# adapter_v1_2.net
KiCad netlist of a schematic drawn in EAGLE
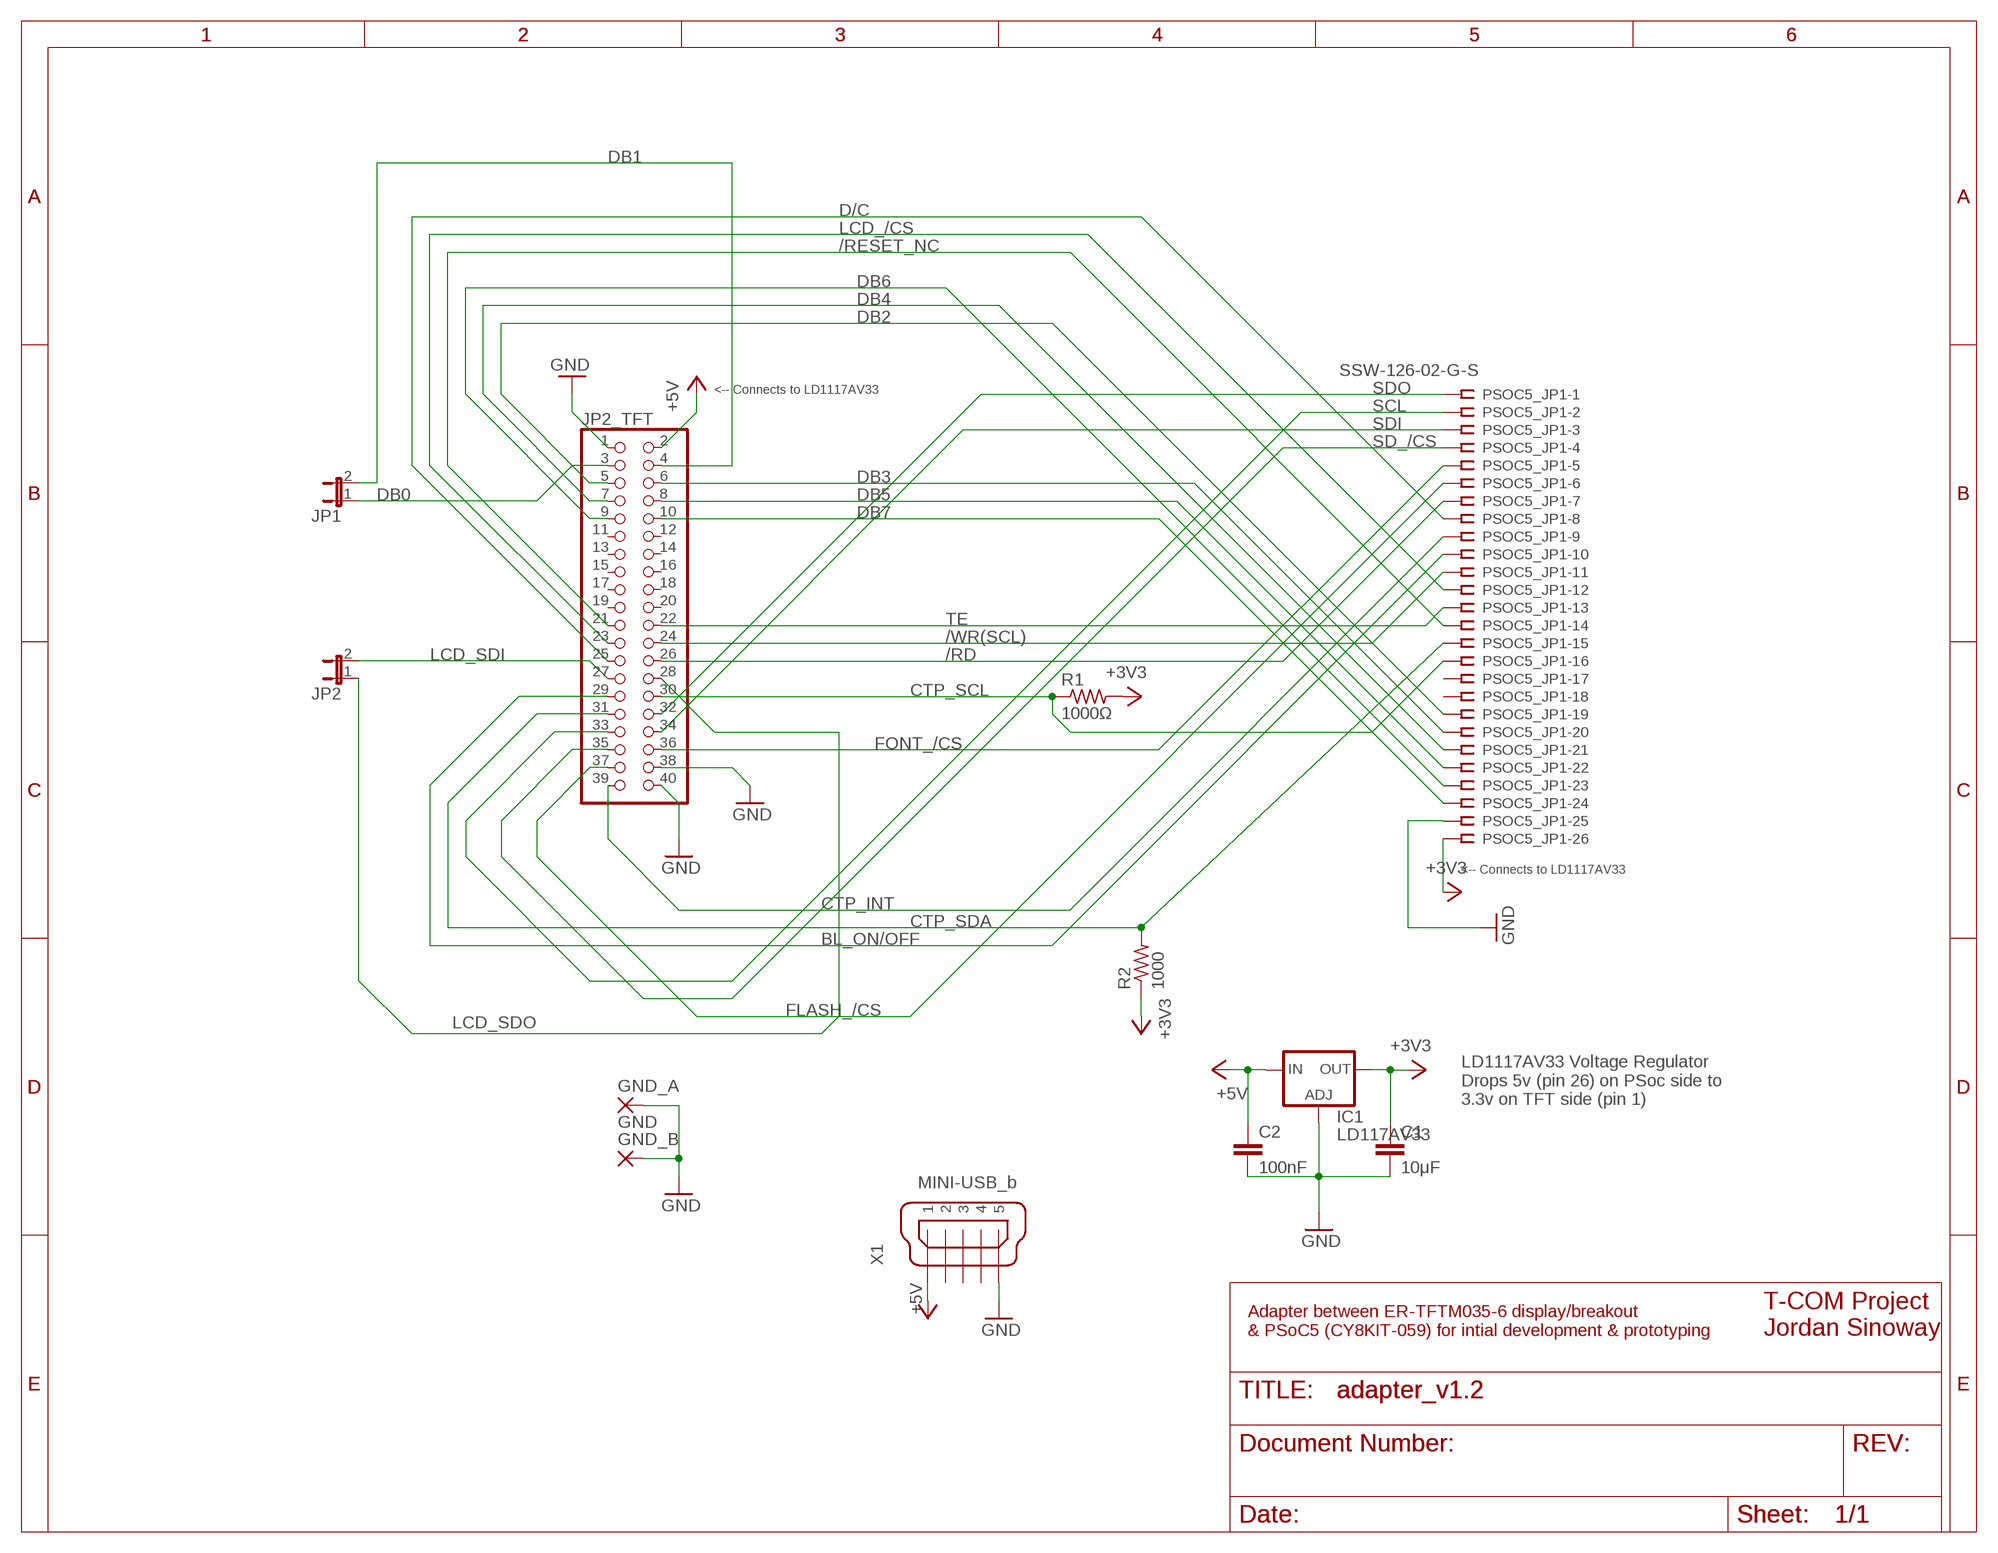
[diagram p0: schematic, sheet 1]

(export (version "E")
  (design (tool "Eeschema 10.0.6"))
  (components
    (comp (ref "C1")
      (value "10μF")
      (footprint "eagle-import:C2.5-2")
      (libsource (lib "eagle-import") (part "C2.5/2"))
    )
    (comp (ref "C2")
      (value "100nF")
      (footprint "eagle-import:C2.5-2")
      (libsource (lib "eagle-import") (part "C2.5/2"))
    )
    (comp (ref "GND_A")
      (value "GND")
      (footprint "eagle-import:SMD2,54-5,08")
      (libsource (lib "eagle-import") (part "SMD5"))
    )
    (comp (ref "GND_B")
      (value "SMD5")
      (footprint "eagle-import:SMD2,54-5,08")
      (libsource (lib "eagle-import") (part "SMD5"))
    )
    (comp (ref "IC1")
      (value "LD117AV33")
      (footprint "eagle-import:TO220L1")
      (libsource (lib "eagle-import") (part "LD117A?V33"))
    )
    (comp (ref "JP1")
      (value "JP1E")
      (footprint "eagle-import:JP1")
      (libsource (lib "eagle-import") (part "JP1E"))
    )
    (comp (ref "JP2")
      (value "JP1E")
      (footprint "eagle-import:JP1")
      (libsource (lib "eagle-import") (part "JP1E"))
    )
    (comp (ref "JP2_TFT")
      (value "PINHD-2X20")
      (footprint "eagle-import:2X20")
      (libsource (lib "eagle-import") (part "PINHD-2X20"))
    )
    (comp (ref "PSOC5_JP1")
      (value "SSW-126-02-G-S")
      (footprint "eagle-import:SSW-126-02-G-S")
      (fields (field (name "MF") "Samtec Inc."))
      (libsource (lib "eagle-import") (part "SSW-126-02-G-S"))
    )
    (comp (ref "R1")
      (value "1000Ω")
      (footprint "eagle-import:0204_7")
      (libsource (lib "eagle-import") (part "R-US_0204/7"))
    )
    (comp (ref "R2")
      (value "1000")
      (footprint "eagle-import:0204_7")
      (libsource (lib "eagle-import") (part "R-US_0204/7"))
    )
    (comp (ref "X1")
      (value "MINI-USB_b")
      (footprint "eagle-import:32005-601")
      (libsource (lib "eagle-import") (part "MINI-USB_SHIELD5P2-32005-601"))
    )
  )
  (nets
    (net (code "1") (name "+3V3") (class "Default")
      (node (ref "C1") (pin "1") (pinfunction "1_1") (pintype "passive"))
      (node (ref "IC1") (pin "2") (pinfunction "OUT_2") (pintype "passive"))
      (node (ref "PSOC5_JP1") (pin "26") (pinfunction "1_26") (pintype "passive"))
      (node (ref "R1") (pin "2") (pinfunction "2_2") (pintype "passive"))
      (node (ref "R2") (pin "1") (pinfunction "1_1") (pintype "passive"))
    )
    (net (code "2") (name "+5V") (class "Default")
      (node (ref "C2") (pin "1") (pinfunction "1_1") (pintype "passive"))
      (node (ref "IC1") (pin "3") (pinfunction "IN_3") (pintype "input"))
      (node (ref "JP2_TFT") (pin "2") (pinfunction "2_2") (pintype "passive"))
      (node (ref "X1") (pin "1") (pinfunction "1_1") (pintype "passive"))
    )
    (net (code "3") (name "/BL_ON{slash}OFF") (class "Default")
      (node (ref "JP2_TFT") (pin "29") (pinfunction "29_29") (pintype "passive"))
      (node (ref "PSOC5_JP1") (pin "10") (pinfunction "1_10") (pintype "passive"))
    )
    (net (code "4") (name "/CTP_INT") (class "Default")
      (node (ref "JP2_TFT") (pin "39") (pinfunction "39_39") (pintype "passive"))
      (node (ref "PSOC5_JP1") (pin "9") (pinfunction "1_9") (pintype "passive"))
    )
    (net (code "5") (name "/CTP_SCL") (class "Default")
      (node (ref "JP2_TFT") (pin "30") (pinfunction "30_30") (pintype "passive"))
      (node (ref "PSOC5_JP1") (pin "16") (pinfunction "1_16") (pintype "passive"))
      (node (ref "R1") (pin "1") (pinfunction "1_1") (pintype "passive"))
    )
    (net (code "6") (name "/CTP_SDA") (class "Default")
      (node (ref "JP2_TFT") (pin "31") (pinfunction "31_31") (pintype "passive"))
      (node (ref "PSOC5_JP1") (pin "15") (pinfunction "1_15") (pintype "passive"))
      (node (ref "R2") (pin "2") (pinfunction "2_2") (pintype "passive"))
    )
    (net (code "7") (name "/DB0") (class "Default")
      (node (ref "JP1") (pin "1") (pinfunction "1_1") (pintype "passive"))
      (node (ref "JP2_TFT") (pin "3") (pinfunction "3_3") (pintype "passive"))
    )
    (net (code "8") (name "/DB1") (class "Default")
      (node (ref "JP1") (pin "2") (pinfunction "2_2") (pintype "passive"))
      (node (ref "JP2_TFT") (pin "4") (pinfunction "4_4") (pintype "passive"))
    )
    (net (code "9") (name "/DB2") (class "Default")
      (node (ref "JP2_TFT") (pin "5") (pinfunction "5_5") (pintype "passive"))
      (node (ref "PSOC5_JP1") (pin "19") (pinfunction "1_19") (pintype "passive"))
    )
    (net (code "10") (name "/DB3") (class "Default")
      (node (ref "JP2_TFT") (pin "6") (pinfunction "6_6") (pintype "passive"))
      (node (ref "PSOC5_JP1") (pin "20") (pinfunction "1_20") (pintype "passive"))
    )
    (net (code "11") (name "/DB4") (class "Default")
      (node (ref "JP2_TFT") (pin "7") (pinfunction "7_7") (pintype "passive"))
      (node (ref "PSOC5_JP1") (pin "21") (pinfunction "1_21") (pintype "passive"))
    )
    (net (code "12") (name "/DB5") (class "Default")
      (node (ref "JP2_TFT") (pin "8") (pinfunction "8_8") (pintype "passive"))
      (node (ref "PSOC5_JP1") (pin "22") (pinfunction "1_22") (pintype "passive"))
    )
    (net (code "13") (name "/DB6") (class "Default")
      (node (ref "JP2_TFT") (pin "9") (pinfunction "9_9") (pintype "passive"))
      (node (ref "PSOC5_JP1") (pin "23") (pinfunction "1_23") (pintype "passive"))
    )
    (net (code "14") (name "/DB7") (class "Default")
      (node (ref "JP2_TFT") (pin "10") (pinfunction "10_10") (pintype "passive"))
      (node (ref "PSOC5_JP1") (pin "24") (pinfunction "1_24") (pintype "passive"))
    )
    (net (code "15") (name "/D{slash}C") (class "Default")
      (node (ref "JP2_TFT") (pin "25") (pinfunction "25_25") (pintype "passive"))
      (node (ref "PSOC5_JP1") (pin "8") (pinfunction "1_8") (pintype "passive"))
    )
    (net (code "16") (name "/FLASH_{slash}CS") (class "Default")
      (node (ref "JP2_TFT") (pin "37") (pinfunction "37_37") (pintype "passive"))
      (node (ref "PSOC5_JP1") (pin "6") (pinfunction "1_6") (pintype "passive"))
    )
    (net (code "17") (name "/FONT_{slash}CS") (class "Default")
      (node (ref "JP2_TFT") (pin "36") (pinfunction "36_36") (pintype "passive"))
      (node (ref "PSOC5_JP1") (pin "5") (pinfunction "1_5") (pintype "passive"))
    )
    (net (code "18") (name "/LCD_SDI") (class "Default")
      (node (ref "JP2") (pin "2") (pinfunction "2_2") (pintype "passive"))
      (node (ref "JP2_TFT") (pin "27") (pinfunction "27_27") (pintype "passive"))
    )
    (net (code "19") (name "/LCD_SDO") (class "Default")
      (node (ref "JP2") (pin "1") (pinfunction "1_1") (pintype "passive"))
      (node (ref "JP2_TFT") (pin "28") (pinfunction "28_28") (pintype "passive"))
    )
    (net (code "20") (name "/LCD_{slash}CS") (class "Default")
      (node (ref "JP2_TFT") (pin "23") (pinfunction "23_23") (pintype "passive"))
      (node (ref "PSOC5_JP1") (pin "12") (pinfunction "1_12") (pintype "passive"))
    )
    (net (code "21") (name "/SCL") (class "Default")
      (node (ref "JP2_TFT") (pin "33") (pinfunction "33_33") (pintype "passive"))
      (node (ref "PSOC5_JP1") (pin "2") (pinfunction "1_2") (pintype "passive"))
    )
    (net (code "22") (name "/SDI") (class "Default")
      (node (ref "JP2_TFT") (pin "34") (pinfunction "34_34") (pintype "passive"))
      (node (ref "PSOC5_JP1") (pin "3") (pinfunction "1_3") (pintype "passive"))
    )
    (net (code "23") (name "/SDO") (class "Default")
      (node (ref "JP2_TFT") (pin "32") (pinfunction "32_32") (pintype "passive"))
      (node (ref "PSOC5_JP1") (pin "1") (pinfunction "1_1") (pintype "passive"))
    )
    (net (code "24") (name "/SD_{slash}CS") (class "Default")
      (node (ref "JP2_TFT") (pin "35") (pinfunction "35_35") (pintype "passive"))
      (node (ref "PSOC5_JP1") (pin "4") (pinfunction "1_4") (pintype "passive"))
    )
    (net (code "25") (name "/TE") (class "Default")
      (node (ref "JP2_TFT") (pin "22") (pinfunction "22_22") (pintype "passive"))
      (node (ref "PSOC5_JP1") (pin "13") (pinfunction "1_13") (pintype "passive"))
    )
    (net (code "26") (name "/{slash}RD") (class "Default")
      (node (ref "JP2_TFT") (pin "26") (pinfunction "26_26") (pintype "passive"))
      (node (ref "PSOC5_JP1") (pin "7") (pinfunction "1_7") (pintype "passive"))
    )
    (net (code "27") (name "/{slash}RESET_NC") (class "Default")
      (node (ref "JP2_TFT") (pin "21") (pinfunction "21_21") (pintype "passive"))
      (node (ref "PSOC5_JP1") (pin "14") (pinfunction "1_14") (pintype "passive"))
    )
    (net (code "28") (name "/{slash}WR(SCL)") (class "Default")
      (node (ref "JP2_TFT") (pin "24") (pinfunction "24_24") (pintype "passive"))
      (node (ref "PSOC5_JP1") (pin "11") (pinfunction "1_11") (pintype "passive"))
    )
    (net (code "29") (name "GND") (class "Default")
      (node (ref "C1") (pin "2") (pinfunction "2_2") (pintype "passive"))
      (node (ref "C2") (pin "2") (pinfunction "2_2") (pintype "passive"))
      (node (ref "GND_A") (pin "1") (pinfunction "P_1") (pintype "passive"))
      (node (ref "GND_B") (pin "1") (pinfunction "P_1") (pintype "passive"))
      (node (ref "IC1") (pin "1") (pinfunction "ADJ_1") (pintype "input"))
      (node (ref "JP2_TFT") (pin "1") (pinfunction "1_1") (pintype "passive"))
      (node (ref "JP2_TFT") (pin "38") (pinfunction "38_38") (pintype "passive"))
      (node (ref "JP2_TFT") (pin "40") (pinfunction "40_40") (pintype "passive"))
      (node (ref "PSOC5_JP1") (pin "25") (pinfunction "1_25") (pintype "passive"))
      (node (ref "X1") (pin "5") (pinfunction "5_5") (pintype "passive"))
    )
    (net (code "30") (name "unconnected-(JP2_TFT-Pad11)") (class "Default")
      (node (ref "JP2_TFT") (pin "11") (pinfunction "11_11") (pintype "passive"))
    )
    (net (code "31") (name "unconnected-(JP2_TFT-Pad12)") (class "Default")
      (node (ref "JP2_TFT") (pin "12") (pinfunction "12_12") (pintype "passive"))
    )
    (net (code "32") (name "unconnected-(JP2_TFT-Pad13)") (class "Default")
      (node (ref "JP2_TFT") (pin "13") (pinfunction "13_13") (pintype "passive"))
    )
    (net (code "33") (name "unconnected-(JP2_TFT-Pad14)") (class "Default")
      (node (ref "JP2_TFT") (pin "14") (pinfunction "14_14") (pintype "passive"))
    )
    (net (code "34") (name "unconnected-(JP2_TFT-Pad15)") (class "Default")
      (node (ref "JP2_TFT") (pin "15") (pinfunction "15_15") (pintype "passive"))
    )
    (net (code "35") (name "unconnected-(JP2_TFT-Pad16)") (class "Default")
      (node (ref "JP2_TFT") (pin "16") (pinfunction "16_16") (pintype "passive"))
    )
    (net (code "36") (name "unconnected-(JP2_TFT-Pad17)") (class "Default")
      (node (ref "JP2_TFT") (pin "17") (pinfunction "17_17") (pintype "passive"))
    )
    (net (code "37") (name "unconnected-(JP2_TFT-Pad18)") (class "Default")
      (node (ref "JP2_TFT") (pin "18") (pinfunction "18_18") (pintype "passive"))
    )
    (net (code "38") (name "unconnected-(JP2_TFT-Pad19)") (class "Default")
      (node (ref "JP2_TFT") (pin "19") (pinfunction "19_19") (pintype "passive"))
    )
    (net (code "39") (name "unconnected-(JP2_TFT-Pad20)") (class "Default")
      (node (ref "JP2_TFT") (pin "20") (pinfunction "20_20") (pintype "passive"))
    )
    (net (code "40") (name "unconnected-(PSOC5_JP1I-1-Pad17)") (class "Default")
      (node (ref "PSOC5_JP1") (pin "17") (pinfunction "1_17") (pintype "passive"))
    )
    (net (code "41") (name "unconnected-(PSOC5_JP1J-1-Pad18)") (class "Default")
      (node (ref "PSOC5_JP1") (pin "18") (pinfunction "1_18") (pintype "passive"))
    )
    (net (code "42") (name "unconnected-(X1-Pad2)") (class "Default")
      (node (ref "X1") (pin "2") (pinfunction "2_2") (pintype "passive"))
    )
    (net (code "43") (name "unconnected-(X1-Pad3)") (class "Default")
      (node (ref "X1") (pin "3") (pinfunction "3_3") (pintype "passive"))
    )
    (net (code "44") (name "unconnected-(X1-Pad4)") (class "Default")
      (node (ref "X1") (pin "4") (pinfunction "4_4") (pintype "passive"))
    )
  )
)
